# osso.net
KiCad netlist of a schematic drawn in EAGLE
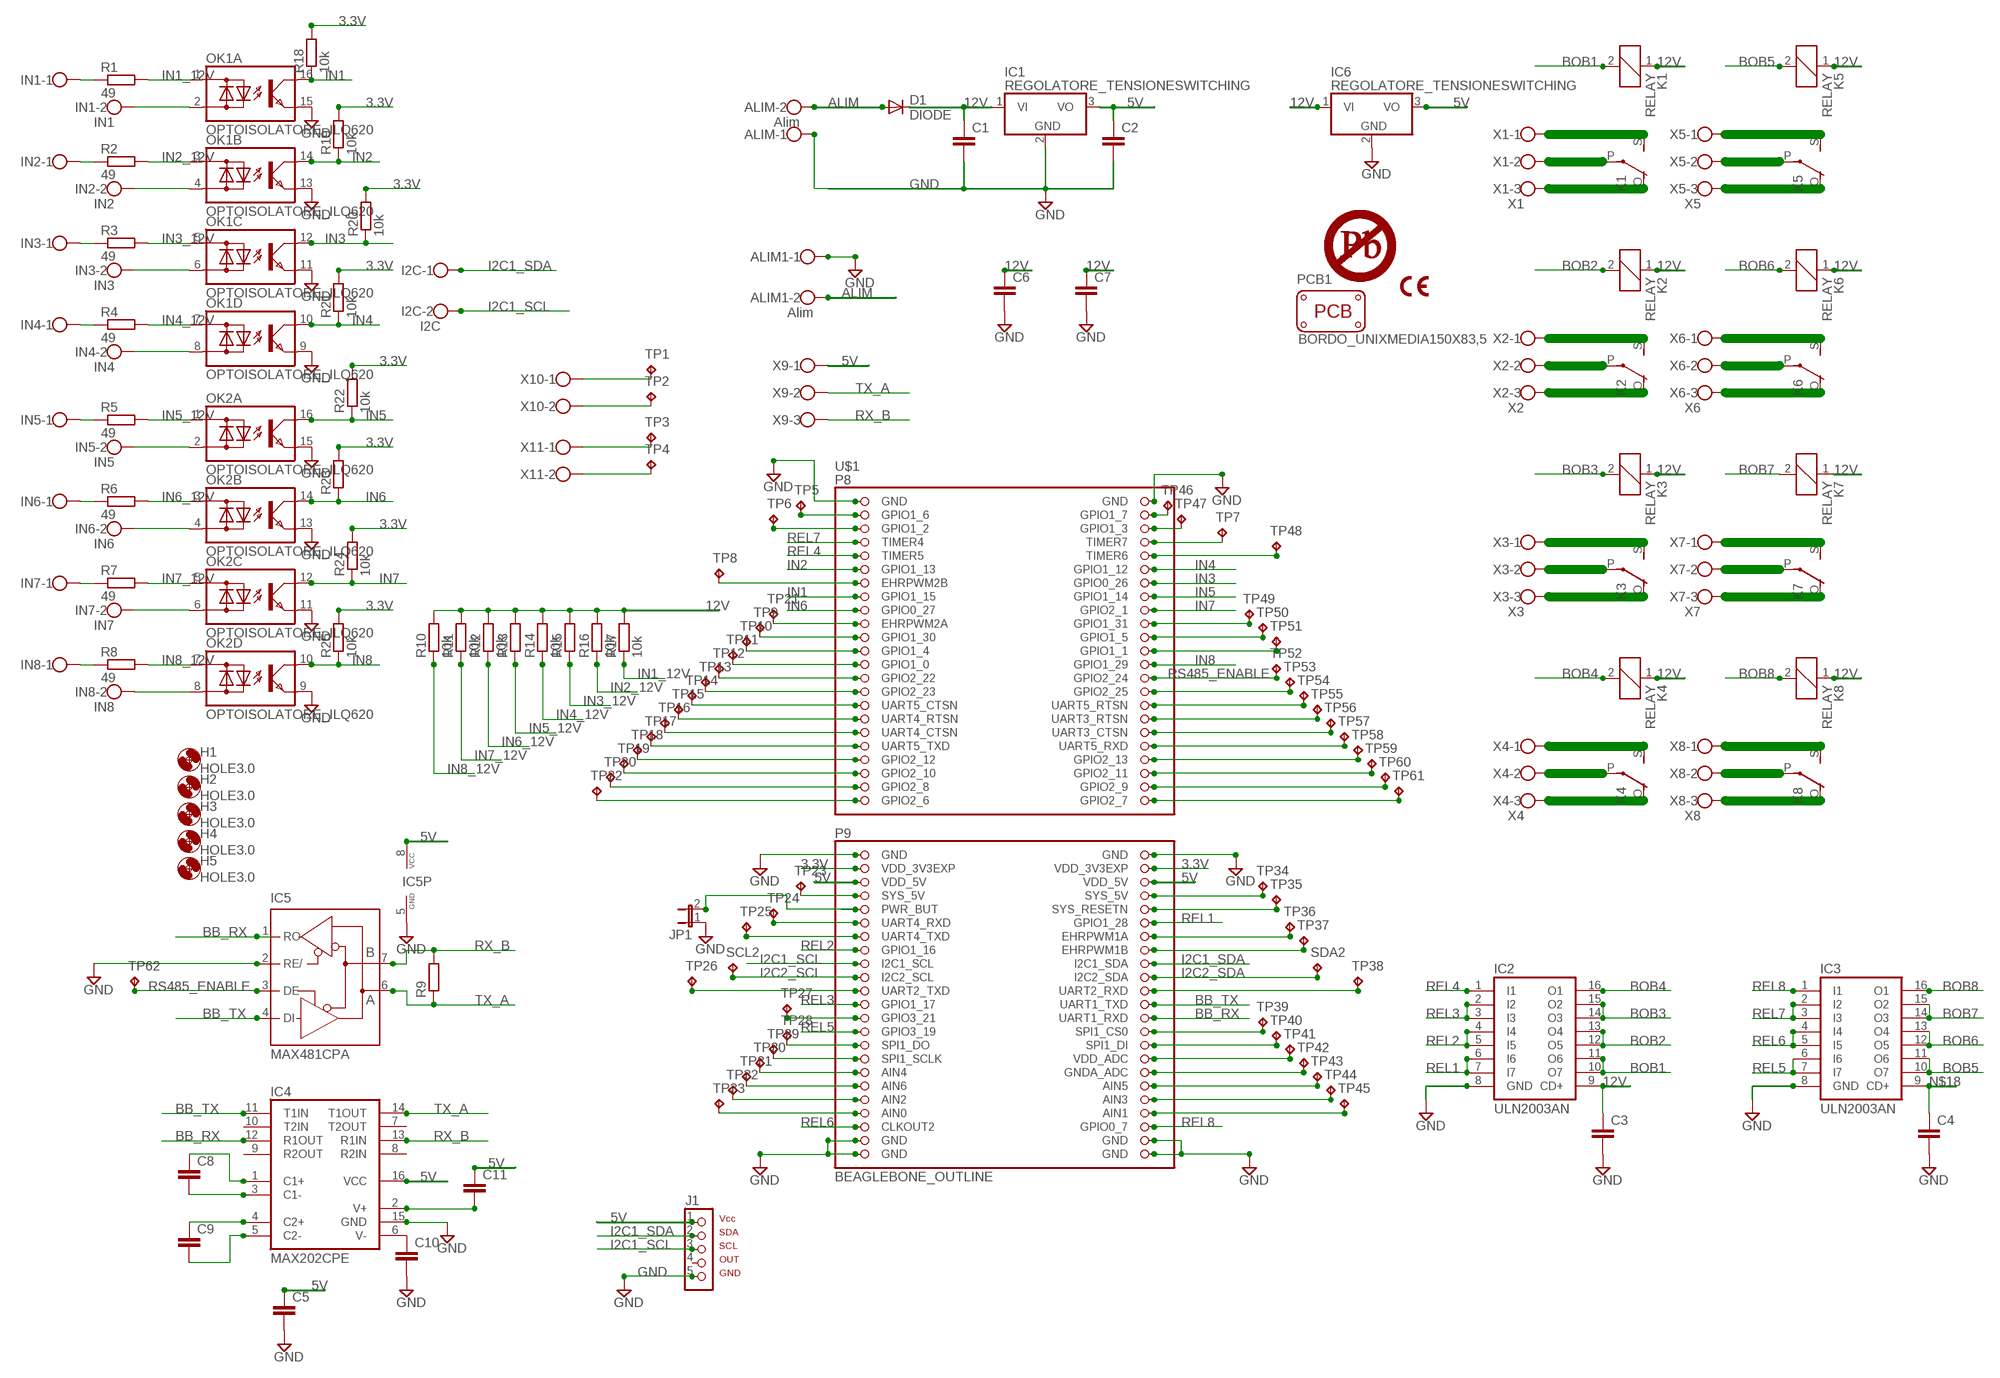
[diagram p0: schematic, sheet 1]

(export (version "E")
  (design (tool "Eeschema 10.0.6"))
  (components
    (comp (ref "ALIM")
      (value "Alim")
      (footprint "eagle-import:W237-102")
      (fields (field (name "MPN") "237-102"))
      (libsource (lib "eagle-import") (part "MORSETTO_2"))
    )
    (comp (ref "ALIM1")
      (value "Alim")
      (footprint "eagle-import:W237-102")
      (fields
        (field (name "MPN") "237-102")
        (field (name "MPN_1") "237-102")
        (field (name "OC_FARNELL") "unknown")
        (field (name "OC_NEWARK") "70K9898")
      )
      (libsource (lib "eagle-import") (part "MORSETTO_2"))
    )
    (comp (ref "C1")
      (value "C5/2.5")
      (footprint "eagle-import:C5B2.5")
      (libsource (lib "eagle-import") (part "C5/2.5"))
    )
    (comp (ref "C2")
      (value "C5/2.5")
      (footprint "eagle-import:C5B2.5")
      (libsource (lib "eagle-import") (part "C5/2.5"))
    )
    (comp (ref "C3")
      (value "C5/2.5")
      (footprint "eagle-import:C5B2.5")
      (libsource (lib "eagle-import") (part "C5/2.5"))
    )
    (comp (ref "C4")
      (value "C5/2.5")
      (footprint "eagle-import:C5B2.5")
      (libsource (lib "eagle-import") (part "C5/2.5"))
    )
    (comp (ref "C5")
      (value "C5/2.5")
      (footprint "eagle-import:C5B2.5")
      (libsource (lib "eagle-import") (part "C5/2.5"))
    )
    (comp (ref "C6")
      (value "C5/2.5")
      (footprint "eagle-import:C5B2.5")
      (libsource (lib "eagle-import") (part "C5/2.5"))
    )
    (comp (ref "C7")
      (value "C5/2.5")
      (footprint "eagle-import:C5B2.5")
      (libsource (lib "eagle-import") (part "C5/2.5"))
    )
    (comp (ref "C8")
      (value "C5/2.5")
      (footprint "eagle-import:C5B2.5")
      (libsource (lib "eagle-import") (part "C5/2.5"))
    )
    (comp (ref "C9")
      (value "C5/2.5")
      (footprint "eagle-import:C5B2.5")
      (libsource (lib "eagle-import") (part "C5/2.5"))
    )
    (comp (ref "C10")
      (value "C5/2.5")
      (footprint "eagle-import:C5B2.5")
      (libsource (lib "eagle-import") (part "C5/2.5"))
    )
    (comp (ref "C11")
      (value "C5/2.5")
      (footprint "eagle-import:C5B2.5")
      (libsource (lib "eagle-import") (part "C5/2.5"))
    )
    (comp (ref "D1")
      (value "DIODE")
      (footprint "eagle-import:DO15-12")
      (libsource (lib "eagle-import") (part "DIODE"))
    )
    (comp (ref "H1")
      (value "HOLE3.0")
      (footprint "eagle-import:3,0")
      (libsource (lib "eagle-import") (part "HOLE3.0"))
    )
    (comp (ref "H2")
      (value "HOLE3.0")
      (footprint "eagle-import:3,0")
      (libsource (lib "eagle-import") (part "HOLE3.0"))
    )
    (comp (ref "H3")
      (value "HOLE3.0")
      (footprint "eagle-import:3,0")
      (libsource (lib "eagle-import") (part "HOLE3.0"))
    )
    (comp (ref "H4")
      (value "HOLE3.0")
      (footprint "eagle-import:3,0")
      (libsource (lib "eagle-import") (part "HOLE3.0"))
    )
    (comp (ref "H5")
      (value "HOLE3.0")
      (footprint "eagle-import:3,0")
      (libsource (lib "eagle-import") (part "HOLE3.0"))
    )
    (comp (ref "I2C")
      (value "I2C")
      (footprint "eagle-import:W237-102")
      (fields
        (field (name "MPN") "237-102")
        (field (name "MPN_1") "237-102")
        (field (name "OC_FARNELL") "unknown")
        (field (name "OC_NEWARK") "70K9898")
      )
      (libsource (lib "eagle-import") (part "MORSETTO_2"))
    )
    (comp (ref "IC1")
      (value "REGOLATORE_TENSIONESWITCHING")
      (footprint "eagle-import:MT6-3")
      (libsource (lib "eagle-import") (part "REGOLATORE_TENSIONESWITCHING"))
    )
    (comp (ref "IC2")
      (value "ULN2003AN")
      (footprint "eagle-import:DIL16")
      (libsource (lib "eagle-import") (part "ULN2003AN"))
    )
    (comp (ref "IC3")
      (value "ULN2003AN")
      (footprint "eagle-import:DIL16")
      (libsource (lib "eagle-import") (part "ULN2003AN"))
    )
    (comp (ref "IC4")
      (value "MAX202CPE")
      (footprint "eagle-import:DIL16")
      (fields (field (name "MF") "MAXIM") (field (name "MPN") "MAX202CPE+"))
      (libsource (lib "eagle-import") (part "MAX202CPE"))
    )
    (comp (ref "IC5")
      (value "MAX481CPA")
      (footprint "eagle-import:DIL08")
      (fields (field (name "MPN") "MAX481CPA+"))
      (libsource (lib "eagle-import") (part "MAX481CPA"))
    )
    (comp (ref "IC6")
      (value "REGOLATORE_TENSIONESWITCHING")
      (footprint "eagle-import:MT6-3")
      (libsource (lib "eagle-import") (part "REGOLATORE_TENSIONESWITCHING"))
    )
    (comp (ref "IN1")
      (value "IN1")
      (footprint "eagle-import:W237-102")
      (fields (field (name "MPN") "237-102"))
      (libsource (lib "eagle-import") (part "MORSETTO_2"))
    )
    (comp (ref "IN2")
      (value "IN2")
      (footprint "eagle-import:W237-102")
      (fields (field (name "MPN") "237-102"))
      (libsource (lib "eagle-import") (part "MORSETTO_2"))
    )
    (comp (ref "IN3")
      (value "IN3")
      (footprint "eagle-import:W237-102")
      (fields (field (name "MPN") "237-102"))
      (libsource (lib "eagle-import") (part "MORSETTO_2"))
    )
    (comp (ref "IN4")
      (value "IN4")
      (footprint "eagle-import:W237-102")
      (fields (field (name "MPN") "237-102"))
      (libsource (lib "eagle-import") (part "MORSETTO_2"))
    )
    (comp (ref "IN5")
      (value "IN5")
      (footprint "eagle-import:W237-102")
      (fields (field (name "MPN") "237-102"))
      (libsource (lib "eagle-import") (part "MORSETTO_2"))
    )
    (comp (ref "IN6")
      (value "IN6")
      (footprint "eagle-import:W237-102")
      (fields (field (name "MPN") "237-102"))
      (libsource (lib "eagle-import") (part "MORSETTO_2"))
    )
    (comp (ref "IN7")
      (value "IN7")
      (footprint "eagle-import:W237-102")
      (fields (field (name "MPN") "237-102"))
      (libsource (lib "eagle-import") (part "MORSETTO_2"))
    )
    (comp (ref "IN8")
      (value "IN8")
      (footprint "eagle-import:W237-102")
      (fields (field (name "MPN") "237-102"))
      (libsource (lib "eagle-import") (part "MORSETTO_2"))
    )
    (comp (ref "J1")
      (value "RTC_MICROROBOT_ALGOZINO-PTH")
      (footprint "eagle-import:RTC_MICROBOT_ALGOZINO")
      (libsource (lib "eagle-import") (part "RTC_MICROROBOT_ALGOZINO-PTH"))
    )
    (comp (ref "JP1")
      (value "JUMPER_2")
      (footprint "eagle-import:JP1")
      (libsource (lib "eagle-import") (part "JUMPER_2"))
    )
    (comp (ref "K1")
      (value "RELAY")
      (footprint "eagle-import:G5LE")
      (libsource (lib "eagle-import") (part "My_Library_RELAY"))
    )
    (comp (ref "K2")
      (value "RELAY")
      (footprint "eagle-import:G5LE")
      (libsource (lib "eagle-import") (part "My_Library_RELAY"))
    )
    (comp (ref "K3")
      (value "RELAY")
      (footprint "eagle-import:G5LE")
      (libsource (lib "eagle-import") (part "My_Library_RELAY"))
    )
    (comp (ref "K4")
      (value "RELAY")
      (footprint "eagle-import:G5LE")
      (libsource (lib "eagle-import") (part "My_Library_RELAY"))
    )
    (comp (ref "K5")
      (value "RELAY")
      (footprint "eagle-import:G5LE")
      (libsource (lib "eagle-import") (part "My_Library_RELAY"))
    )
    (comp (ref "K6")
      (value "RELAY")
      (footprint "eagle-import:G5LE")
      (libsource (lib "eagle-import") (part "My_Library_RELAY"))
    )
    (comp (ref "K7")
      (value "RELAY")
      (footprint "eagle-import:G5LE")
      (libsource (lib "eagle-import") (part "RELAY"))
    )
    (comp (ref "K8")
      (value "RELAY")
      (footprint "eagle-import:G5LE")
      (libsource (lib "eagle-import") (part "My_Library_RELAY"))
    )
    (comp (ref "OK1")
      (value "OPTOISOLATORE_ILQ620")
      (footprint "eagle-import:DIL16")
      (fields (field (name "MF") "VISHAY/TELEFUNKEN") (field (name "MPN") "ILQ620"))
      (libsource (lib "eagle-import") (part "OPTOISOLATORE_ILQ620"))
    )
    (comp (ref "OK2")
      (value "OPTOISOLATORE_ILQ620")
      (footprint "eagle-import:DIL16")
      (fields (field (name "MF") "VISHAY/TELEFUNKEN") (field (name "MPN") "ILQ620"))
      (libsource (lib "eagle-import") (part "OPTOISOLATORE_ILQ620"))
    )
    (comp (ref "PCB1")
      (value "BORDO_UNIXMEDIA150X83,5")
      (footprint "eagle-import:BORD_UNIXMEDIA")
      (libsource (lib "eagle-import") (part "BORDO_UNIXMEDIA150X83,5"))
    )
    (comp (ref "R1")
      (value "49")
      (footprint "eagle-import:0204_7")
      (libsource (lib "eagle-import") (part "RESISTOR0204/7"))
    )
    (comp (ref "R2")
      (value "49")
      (footprint "eagle-import:0204_7")
      (libsource (lib "eagle-import") (part "RESISTOR0204/7"))
    )
    (comp (ref "R3")
      (value "49")
      (footprint "eagle-import:0204_7")
      (libsource (lib "eagle-import") (part "RESISTOR0204/7"))
    )
    (comp (ref "R4")
      (value "49")
      (footprint "eagle-import:0204_7")
      (libsource (lib "eagle-import") (part "RESISTOR0204/7"))
    )
    (comp (ref "R5")
      (value "49")
      (footprint "eagle-import:0204_7")
      (libsource (lib "eagle-import") (part "RESISTOR0204/7"))
    )
    (comp (ref "R6")
      (value "49")
      (footprint "eagle-import:0204_7")
      (libsource (lib "eagle-import") (part "RESISTOR0204/7"))
    )
    (comp (ref "R7")
      (value "49")
      (footprint "eagle-import:0204_7")
      (libsource (lib "eagle-import") (part "RESISTOR0204/7"))
    )
    (comp (ref "R8")
      (value "49")
      (footprint "eagle-import:0204_7")
      (libsource (lib "eagle-import") (part "RESISTOR0204/7"))
    )
    (comp (ref "R9")
      (value "RESISTOR0204/7")
      (footprint "eagle-import:0204_7")
      (libsource (lib "eagle-import") (part "RESISTOR0204/7"))
    )
    (comp (ref "R10")
      (value "10k")
      (footprint "eagle-import:0204_7")
      (libsource (lib "eagle-import") (part "RESISTOR0204/7"))
    )
    (comp (ref "R11")
      (value "10k")
      (footprint "eagle-import:0204_7")
      (libsource (lib "eagle-import") (part "RESISTOR0204/7"))
    )
    (comp (ref "R12")
      (value "10k")
      (footprint "eagle-import:0204_7")
      (libsource (lib "eagle-import") (part "RESISTOR0204/7"))
    )
    (comp (ref "R13")
      (value "RESISTOR0204/7")
      (footprint "eagle-import:0204_7")
      (libsource (lib "eagle-import") (part "RESISTOR0204/7"))
    )
    (comp (ref "R14")
      (value "10k")
      (footprint "eagle-import:0204_7")
      (libsource (lib "eagle-import") (part "RESISTOR0204/7"))
    )
    (comp (ref "R15")
      (value "RESISTOR0204/7")
      (footprint "eagle-import:0204_7")
      (libsource (lib "eagle-import") (part "RESISTOR0204/7"))
    )
    (comp (ref "R16")
      (value "10k")
      (footprint "eagle-import:0204_7")
      (libsource (lib "eagle-import") (part "RESISTOR0204/7"))
    )
    (comp (ref "R17")
      (value "10k")
      (footprint "eagle-import:0204_7")
      (libsource (lib "eagle-import") (part "RESISTOR0204/7"))
    )
    (comp (ref "R18")
      (value "10k")
      (footprint "eagle-import:0204_7")
      (libsource (lib "eagle-import") (part "RESISTOR0204/7"))
    )
    (comp (ref "R19")
      (value "10k")
      (footprint "eagle-import:0204_7")
      (libsource (lib "eagle-import") (part "RESISTOR0204/7"))
    )
    (comp (ref "R20")
      (value "10k")
      (footprint "eagle-import:0204_7")
      (libsource (lib "eagle-import") (part "RESISTOR0204/7"))
    )
    (comp (ref "R21")
      (value "10k")
      (footprint "eagle-import:0204_7")
      (libsource (lib "eagle-import") (part "RESISTOR0204/7"))
    )
    (comp (ref "R22")
      (value "10k")
      (footprint "eagle-import:0204_7")
      (libsource (lib "eagle-import") (part "RESISTOR0204/7"))
    )
    (comp (ref "R23")
      (value "RESISTOR0204/7")
      (footprint "eagle-import:0204_7")
      (libsource (lib "eagle-import") (part "RESISTOR0204/7"))
    )
    (comp (ref "R24")
      (value "10k")
      (footprint "eagle-import:0204_7")
      (libsource (lib "eagle-import") (part "RESISTOR0204/7"))
    )
    (comp (ref "R25")
      (value "10k")
      (footprint "eagle-import:0204_7")
      (libsource (lib "eagle-import") (part "RESISTOR0204/7"))
    )
    (comp (ref "SCL2")
      (value "TPPAD1-13")
      (footprint "eagle-import:TEST_POINT")
      (libsource (lib "eagle-import") (part "TPPAD1-13"))
    )
    (comp (ref "SDA2")
      (value "TP1")
      (footprint "eagle-import:TEST_POINT")
      (libsource (lib "eagle-import") (part "TPPAD1-13"))
    )
    (comp (ref "SS1")
      (value "CE-MARK")
      (footprint "eagle-import:CE-MARK-0.2")
      (libsource (lib "eagle-import") (part "CE-MARK"))
    )
    (comp (ref "SS2")
      (value "PB-MARK")
      (footprint "eagle-import:PB-MARK-0.2")
      (libsource (lib "eagle-import") (part "PB-MARK"))
    )
    (comp (ref "TP1")
      (value "TPPAD1-13")
      (footprint "eagle-import:TEST_POINT")
      (libsource (lib "eagle-import") (part "TPPAD1-13"))
    )
    (comp (ref "TP2")
      (value "TPPAD1-13")
      (footprint "eagle-import:TEST_POINT")
      (libsource (lib "eagle-import") (part "TPPAD1-13"))
    )
    (comp (ref "TP3")
      (value "TPPAD1-13")
      (footprint "eagle-import:TEST_POINT")
      (libsource (lib "eagle-import") (part "TPPAD1-13"))
    )
    (comp (ref "TP4")
      (value "TPPAD1-13")
      (footprint "eagle-import:TEST_POINT")
      (libsource (lib "eagle-import") (part "TPPAD1-13"))
    )
    (comp (ref "TP5")
      (value "TPPAD1-13")
      (footprint "eagle-import:TEST_POINT")
      (libsource (lib "eagle-import") (part "TPPAD1-13"))
    )
    (comp (ref "TP6")
      (value "TPPAD1-13")
      (footprint "eagle-import:TEST_POINT")
      (libsource (lib "eagle-import") (part "TPPAD1-13"))
    )
    (comp (ref "TP7")
      (value "TPPAD1-13")
      (footprint "eagle-import:TEST_POINT")
      (libsource (lib "eagle-import") (part "TPPAD1-13"))
    )
    (comp (ref "TP8")
      (value "TPPAD1-13")
      (footprint "eagle-import:TEST_POINT")
      (libsource (lib "eagle-import") (part "TPPAD1-13"))
    )
    (comp (ref "TP9")
      (value "TPPAD1-13")
      (footprint "eagle-import:TEST_POINT")
      (libsource (lib "eagle-import") (part "TPPAD1-13"))
    )
    (comp (ref "TP10")
      (value "TPPAD1-13")
      (footprint "eagle-import:TEST_POINT")
      (libsource (lib "eagle-import") (part "TPPAD1-13"))
    )
    (comp (ref "TP11")
      (value "TPPAD1-13")
      (footprint "eagle-import:TEST_POINT")
      (libsource (lib "eagle-import") (part "TPPAD1-13"))
    )
    (comp (ref "TP12")
      (value "TPPAD1-13")
      (footprint "eagle-import:TEST_POINT")
      (libsource (lib "eagle-import") (part "TPPAD1-13"))
    )
    (comp (ref "TP13")
      (value "TPPAD1-13")
      (footprint "eagle-import:TEST_POINT")
      (libsource (lib "eagle-import") (part "TPPAD1-13"))
    )
    (comp (ref "TP14")
      (value "TPPAD1-13")
      (footprint "eagle-import:TEST_POINT")
      (libsource (lib "eagle-import") (part "TPPAD1-13"))
    )
    (comp (ref "TP15")
      (value "TPPAD1-13")
      (footprint "eagle-import:TEST_POINT")
      (libsource (lib "eagle-import") (part "TPPAD1-13"))
    )
    (comp (ref "TP16")
      (value "TPPAD1-13")
      (footprint "eagle-import:TEST_POINT")
      (libsource (lib "eagle-import") (part "TPPAD1-13"))
    )
    (comp (ref "TP17")
      (value "TPPAD1-13")
      (footprint "eagle-import:TEST_POINT")
      (libsource (lib "eagle-import") (part "TPPAD1-13"))
    )
    (comp (ref "TP18")
      (value "TPPAD1-13")
      (footprint "eagle-import:TEST_POINT")
      (libsource (lib "eagle-import") (part "TPPAD1-13"))
    )
    (comp (ref "TP19")
      (value "TPPAD1-13")
      (footprint "eagle-import:TEST_POINT")
      (libsource (lib "eagle-import") (part "TPPAD1-13"))
    )
    (comp (ref "TP20")
      (value "TPPAD1-13")
      (footprint "eagle-import:TEST_POINT")
      (libsource (lib "eagle-import") (part "TPPAD1-13"))
    )
    (comp (ref "TP21")
      (value "TPPAD1-13")
      (footprint "eagle-import:TEST_POINT")
      (libsource (lib "eagle-import") (part "TPPAD1-13"))
    )
    (comp (ref "TP22")
      (value "TPPAD1-13")
      (footprint "eagle-import:TEST_POINT")
      (libsource (lib "eagle-import") (part "TPPAD1-13"))
    )
    (comp (ref "TP23")
      (value "TPPAD1-13")
      (footprint "eagle-import:TEST_POINT")
      (libsource (lib "eagle-import") (part "TPPAD1-13"))
    )
    (comp (ref "TP24")
      (value "TPPAD1-13")
      (footprint "eagle-import:TEST_POINT")
      (libsource (lib "eagle-import") (part "TPPAD1-13"))
    )
    (comp (ref "TP25")
      (value "TPPAD1-13")
      (footprint "eagle-import:TEST_POINT")
      (libsource (lib "eagle-import") (part "TPPAD1-13"))
    )
    (comp (ref "TP26")
      (value "TPPAD1-13")
      (footprint "eagle-import:TEST_POINT")
      (libsource (lib "eagle-import") (part "TPPAD1-13"))
    )
    (comp (ref "TP27")
      (value "TPPAD1-13")
      (footprint "eagle-import:TEST_POINT")
      (libsource (lib "eagle-import") (part "TPPAD1-13"))
    )
    (comp (ref "TP28")
      (value "TPPAD1-13")
      (footprint "eagle-import:TEST_POINT")
      (libsource (lib "eagle-import") (part "TPPAD1-13"))
    )
    (comp (ref "TP29")
      (value "TPPAD1-13")
      (footprint "eagle-import:TEST_POINT")
      (libsource (lib "eagle-import") (part "TPPAD1-13"))
    )
    (comp (ref "TP30")
      (value "TPPAD1-13")
      (footprint "eagle-import:TEST_POINT")
      (libsource (lib "eagle-import") (part "TPPAD1-13"))
    )
    (comp (ref "TP31")
      (value "TPPAD1-13")
      (footprint "eagle-import:TEST_POINT")
      (libsource (lib "eagle-import") (part "TPPAD1-13"))
    )
    (comp (ref "TP32")
      (value "TPPAD1-13")
      (footprint "eagle-import:TEST_POINT")
      (libsource (lib "eagle-import") (part "TPPAD1-13"))
    )
    (comp (ref "TP33")
      (value "TPPAD1-13")
      (footprint "eagle-import:TEST_POINT")
      (libsource (lib "eagle-import") (part "TPPAD1-13"))
    )
    (comp (ref "TP34")
      (value "TPPAD1-13")
      (footprint "eagle-import:TEST_POINT")
      (libsource (lib "eagle-import") (part "TPPAD1-13"))
    )
    (comp (ref "TP35")
      (value "TPPAD1-13")
      (footprint "eagle-import:TEST_POINT")
      (libsource (lib "eagle-import") (part "TPPAD1-13"))
    )
    (comp (ref "TP36")
      (value "TPPAD1-13")
      (footprint "eagle-import:TEST_POINT")
      (libsource (lib "eagle-import") (part "TPPAD1-13"))
    )
    (comp (ref "TP37")
      (value "TPPAD1-13")
      (footprint "eagle-import:TEST_POINT")
      (libsource (lib "eagle-import") (part "TPPAD1-13"))
    )
    (comp (ref "TP38")
      (value "TPPAD1-13")
      (footprint "eagle-import:TEST_POINT")
      (libsource (lib "eagle-import") (part "TPPAD1-13"))
    )
    (comp (ref "TP39")
      (value "TPPAD1-13")
      (footprint "eagle-import:TEST_POINT")
      (libsource (lib "eagle-import") (part "TPPAD1-13"))
    )
    (comp (ref "TP40")
      (value "TPPAD1-13")
      (footprint "eagle-import:TEST_POINT")
      (libsource (lib "eagle-import") (part "TPPAD1-13"))
    )
    (comp (ref "TP41")
      (value "TPPAD1-13")
      (footprint "eagle-import:TEST_POINT")
      (libsource (lib "eagle-import") (part "TPPAD1-13"))
    )
    (comp (ref "TP42")
      (value "TPPAD1-13")
      (footprint "eagle-import:TEST_POINT")
      (libsource (lib "eagle-import") (part "TPPAD1-13"))
    )
    (comp (ref "TP43")
      (value "TPPAD1-13")
      (footprint "eagle-import:TEST_POINT")
      (libsource (lib "eagle-import") (part "TPPAD1-13"))
    )
    (comp (ref "TP44")
      (value "TPPAD1-13")
      (footprint "eagle-import:TEST_POINT")
      (libsource (lib "eagle-import") (part "TPPAD1-13"))
    )
    (comp (ref "TP45")
      (value "TPPAD1-13")
      (footprint "eagle-import:TEST_POINT")
      (libsource (lib "eagle-import") (part "TPPAD1-13"))
    )
    (comp (ref "TP46")
      (value "TPPAD1-13")
      (footprint "eagle-import:TEST_POINT")
      (libsource (lib "eagle-import") (part "TPPAD1-13"))
    )
    (comp (ref "TP47")
      (value "TPPAD1-13")
      (footprint "eagle-import:TEST_POINT")
      (libsource (lib "eagle-import") (part "TPPAD1-13"))
    )
    (comp (ref "TP48")
      (value "TPPAD1-13")
      (footprint "eagle-import:TEST_POINT")
      (libsource (lib "eagle-import") (part "TPPAD1-13"))
    )
    (comp (ref "TP49")
      (value "TPPAD1-13")
      (footprint "eagle-import:TEST_POINT")
      (libsource (lib "eagle-import") (part "TPPAD1-13"))
    )
    (comp (ref "TP50")
      (value "TPPAD1-13")
      (footprint "eagle-import:TEST_POINT")
      (libsource (lib "eagle-import") (part "TPPAD1-13"))
    )
    (comp (ref "TP51")
      (value "TPPAD1-13")
      (footprint "eagle-import:TEST_POINT")
      (libsource (lib "eagle-import") (part "TPPAD1-13"))
    )
    (comp (ref "TP52")
      (value "TPPAD1-13")
      (footprint "eagle-import:TEST_POINT")
      (libsource (lib "eagle-import") (part "TPPAD1-13"))
    )
    (comp (ref "TP53")
      (value "TPPAD1-13")
      (footprint "eagle-import:TEST_POINT")
      (libsource (lib "eagle-import") (part "TPPAD1-13"))
    )
    (comp (ref "TP54")
      (value "TPPAD1-13")
      (footprint "eagle-import:TEST_POINT")
      (libsource (lib "eagle-import") (part "TPPAD1-13"))
    )
    (comp (ref "TP55")
      (value "TPPAD1-13")
      (footprint "eagle-import:TEST_POINT")
      (libsource (lib "eagle-import") (part "TPPAD1-13"))
    )
    (comp (ref "TP56")
      (value "TPPAD1-13")
      (footprint "eagle-import:TEST_POINT")
      (libsource (lib "eagle-import") (part "TPPAD1-13"))
    )
    (comp (ref "TP57")
      (value "TPPAD1-13")
      (footprint "eagle-import:TEST_POINT")
      (libsource (lib "eagle-import") (part "TPPAD1-13"))
    )
    (comp (ref "TP58")
      (value "TPPAD1-13")
      (footprint "eagle-import:TEST_POINT")
      (libsource (lib "eagle-import") (part "TPPAD1-13"))
    )
    (comp (ref "TP59")
      (value "TPPAD1-13")
      (footprint "eagle-import:TEST_POINT")
      (libsource (lib "eagle-import") (part "TPPAD1-13"))
    )
    (comp (ref "TP60")
      (value "TPPAD1-13")
      (footprint "eagle-import:TEST_POINT")
      (libsource (lib "eagle-import") (part "TPPAD1-13"))
    )
    (comp (ref "TP61")
      (value "TPPAD1-13")
      (footprint "eagle-import:TEST_POINT")
      (libsource (lib "eagle-import") (part "TPPAD1-13"))
    )
    (comp (ref "TP62")
      (value "TPPAD1-13")
      (footprint "eagle-import:TEST_POINT")
      (libsource (lib "eagle-import") (part "TPPAD1-13"))
    )
    (comp (ref "U$1")
      (value "BEAGLEBONE_OUTLINE")
      (footprint "eagle-import:BEAGLEBONE_SHIELD")
      (libsource (lib "eagle-import") (part "BEAGLEBONE_OUTLINE"))
    )
    (comp (ref "X1")
      (value "X1")
      (footprint "eagle-import:W237-103")
      (fields (field (name "MPN") "237-103"))
      (libsource (lib "eagle-import") (part "MORSETTO_3"))
    )
    (comp (ref "X2")
      (value "X2")
      (footprint "eagle-import:W237-103")
      (fields (field (name "MPN") "237-103"))
      (libsource (lib "eagle-import") (part "MORSETTO_3"))
    )
    (comp (ref "X3")
      (value "X3")
      (footprint "eagle-import:W237-103")
      (fields (field (name "MPN") "237-103"))
      (libsource (lib "eagle-import") (part "MORSETTO_3"))
    )
    (comp (ref "X4")
      (value "X4")
      (footprint "eagle-import:W237-103")
      (fields (field (name "MPN") "237-103"))
      (libsource (lib "eagle-import") (part "MORSETTO_3"))
    )
    (comp (ref "X5")
      (value "X5")
      (footprint "eagle-import:W237-103")
      (fields (field (name "MPN") "237-103"))
      (libsource (lib "eagle-import") (part "MORSETTO_3"))
    )
    (comp (ref "X6")
      (value "X6")
      (footprint "eagle-import:W237-103")
      (fields (field (name "MPN") "237-103"))
      (libsource (lib "eagle-import") (part "MORSETTO_3"))
    )
    (comp (ref "X7")
      (value "X7")
      (footprint "eagle-import:W237-103")
      (fields (field (name "MPN") "237-103"))
      (libsource (lib "eagle-import") (part "MORSETTO_3"))
    )
    (comp (ref "X8")
      (value "X8")
      (footprint "eagle-import:W237-103")
      (fields (field (name "MPN") "237-103"))
      (libsource (lib "eagle-import") (part "MORSETTO_3"))
    )
    (comp (ref "X9")
      (value "MORSETTO_3")
      (footprint "eagle-import:W237-103")
      (fields (field (name "MPN") "237-103"))
      (libsource (lib "eagle-import") (part "MORSETTO_3"))
    )
    (comp (ref "X10")
      (value "MORSETTO_2")
      (footprint "eagle-import:W237-102")
      (fields (field (name "MPN") "237-102"))
      (libsource (lib "eagle-import") (part "MORSETTO_2"))
    )
    (comp (ref "X11")
      (value "MORSETTO_2")
      (footprint "eagle-import:W237-102")
      (fields (field (name "MPN") "237-102"))
      (libsource (lib "eagle-import") (part "MORSETTO_2"))
    )
  )
  (nets
    (net (code "1") (name "/3.3V") (class "Default")
      (node (ref "R18") (pin "2") (pinfunction "2_2") (pintype "passive"))
      (node (ref "R19") (pin "2") (pinfunction "2_2") (pintype "passive"))
      (node (ref "R20") (pin "2") (pinfunction "2_2") (pintype "passive"))
      (node (ref "R21") (pin "2") (pinfunction "2_2") (pintype "passive"))
      (node (ref "R22") (pin "2") (pinfunction "2_2") (pintype "passive"))
      (node (ref "R23") (pin "2") (pinfunction "2_2") (pintype "passive"))
      (node (ref "R24") (pin "2") (pinfunction "2_2") (pintype "passive"))
      (node (ref "R25") (pin "2") (pinfunction "2_2") (pintype "passive"))
      (node (ref "U$1") (pin "49") (pinfunction "VDD_3V3EXP_49") (pintype "power_in"))
      (node (ref "U$1") (pin "50") (pinfunction "VDD_3V3EXP_50") (pintype "power_in"))
    )
    (net (code "2") (name "/5V") (class "Default")
      (node (ref "C11") (pin "1") (pinfunction "1_1") (pintype "passive"))
      (node (ref "C2") (pin "1") (pinfunction "1_1") (pintype "passive"))
      (node (ref "C5") (pin "1") (pinfunction "1_1") (pintype "passive"))
      (node (ref "IC1") (pin "3") (pinfunction "VO_3") (pintype "passive"))
      (node (ref "IC4") (pin "16") (pinfunction "VCC_16") (pintype "power_in"))
      (node (ref "IC5") (pin "8") (pinfunction "VCC_8") (pintype "power_in"))
      (node (ref "IC6") (pin "3") (pinfunction "VO_3") (pintype "passive"))
      (node (ref "J1") (pin "1") (pinfunction "1_1") (pintype "bidirectional"))
      (node (ref "U$1") (pin "51") (pinfunction "VDD_5V_51") (pintype "power_in"))
      (node (ref "U$1") (pin "52") (pinfunction "VDD_5V_52") (pintype "power_in"))
      (node (ref "X9") (pin "1") (pinfunction "KL_1") (pintype "passive"))
    )
    (net (code "3") (name "/12V") (class "Default")
      (node (ref "C1") (pin "1") (pinfunction "1_1") (pintype "passive"))
      (node (ref "C3") (pin "1") (pinfunction "1_1") (pintype "passive"))
      (node (ref "C6") (pin "1") (pinfunction "1_1") (pintype "passive"))
      (node (ref "C7") (pin "1") (pinfunction "1_1") (pintype "passive"))
      (node (ref "D1") (pin "C") (pinfunction "C_C") (pintype "passive"))
      (node (ref "IC1") (pin "1") (pinfunction "VI_1") (pintype "input"))
      (node (ref "IC2") (pin "9") (pinfunction "CD+_9") (pintype "passive"))
      (node (ref "IC6") (pin "1") (pinfunction "VI_1") (pintype "input"))
      (node (ref "K1") (pin "1") (pinfunction "1_1") (pintype "passive"))
      (node (ref "K2") (pin "1") (pinfunction "1_1") (pintype "passive"))
      (node (ref "K3") (pin "1") (pinfunction "1_1") (pintype "passive"))
      (node (ref "K4") (pin "1") (pinfunction "1_1") (pintype "passive"))
      (node (ref "K5") (pin "1") (pinfunction "1_1") (pintype "passive"))
      (node (ref "K6") (pin "1") (pinfunction "1_1") (pintype "passive"))
      (node (ref "K7") (pin "1") (pinfunction "1_1") (pintype "passive"))
      (node (ref "K8") (pin "1") (pinfunction "1_1") (pintype "passive"))
      (node (ref "R10") (pin "2") (pinfunction "2_2") (pintype "passive"))
      (node (ref "R11") (pin "2") (pinfunction "2_2") (pintype "passive"))
      (node (ref "R12") (pin "2") (pinfunction "2_2") (pintype "passive"))
      (node (ref "R13") (pin "2") (pinfunction "2_2") (pintype "passive"))
      (node (ref "R14") (pin "2") (pinfunction "2_2") (pintype "passive"))
      (node (ref "R15") (pin "2") (pinfunction "2_2") (pintype "passive"))
      (node (ref "R16") (pin "2") (pinfunction "2_2") (pintype "passive"))
      (node (ref "R17") (pin "2") (pinfunction "2_2") (pintype "passive"))
    )
    (net (code "4") (name "/ALIM") (class "Default")
      (node (ref "ALIM") (pin "2") (pinfunction "KL_2") (pintype "passive"))
      (node (ref "ALIM1") (pin "2") (pinfunction "KL_2") (pintype "passive"))
      (node (ref "D1") (pin "A") (pinfunction "A_A") (pintype "passive"))
    )
    (net (code "5") (name "/BB_RX") (class "Default")
      (node (ref "IC4") (pin "12") (pinfunction "R1OUT_12") (pintype "output"))
      (node (ref "IC5") (pin "1") (pinfunction "RO_1") (pintype "output"))
      (node (ref "U$1") (pin "72") (pinfunction "UART1_RXD_72") (pintype "passive"))
    )
    (net (code "6") (name "/BB_TX") (class "Default")
      (node (ref "IC4") (pin "11") (pinfunction "T1IN_11") (pintype "input"))
      (node (ref "IC5") (pin "4") (pinfunction "DI_4") (pintype "input"))
      (node (ref "U$1") (pin "70") (pinfunction "UART1_TXD_70") (pintype "passive"))
    )
    (net (code "7") (name "/BOB1") (class "Default")
      (node (ref "IC2") (pin "10") (pinfunction "O7_10") (pintype "open_collector"))
      (node (ref "IC2") (pin "11") (pinfunction "O6_11") (pintype "open_collector"))
      (node (ref "K1") (pin "2") (pinfunction "2_2") (pintype "passive"))
    )
    (net (code "8") (name "/BOB2") (class "Default")
      (node (ref "IC2") (pin "12") (pinfunction "O5_12") (pintype "open_collector"))
      (node (ref "IC2") (pin "13") (pinfunction "O4_13") (pintype "open_collector"))
      (node (ref "K2") (pin "2") (pinfunction "2_2") (pintype "passive"))
    )
    (net (code "9") (name "/BOB3") (class "Default")
      (node (ref "IC2") (pin "14") (pinfunction "O3_14") (pintype "open_collector"))
      (node (ref "IC2") (pin "15") (pinfunction "O2_15") (pintype "open_collector"))
      (node (ref "K3") (pin "2") (pinfunction "2_2") (pintype "passive"))
    )
    (net (code "10") (name "/BOB4") (class "Default")
      (node (ref "IC2") (pin "16") (pinfunction "O1_16") (pintype "open_collector"))
      (node (ref "K4") (pin "2") (pinfunction "2_2") (pintype "passive"))
    )
    (net (code "11") (name "/BOB5") (class "Default")
      (node (ref "IC3") (pin "10") (pinfunction "O7_10") (pintype "open_collector"))
      (node (ref "IC3") (pin "11") (pinfunction "O6_11") (pintype "open_collector"))
      (node (ref "K5") (pin "2") (pinfunction "2_2") (pintype "passive"))
    )
    (net (code "12") (name "/BOB6") (class "Default")
      (node (ref "IC3") (pin "12") (pinfunction "O5_12") (pintype "open_collector"))
      (node (ref "IC3") (pin "13") (pinfunction "O4_13") (pintype "open_collector"))
      (node (ref "K6") (pin "2") (pinfunction "2_2") (pintype "passive"))
    )
    (net (code "13") (name "/BOB7") (class "Default")
      (node (ref "IC3") (pin "14") (pinfunction "O3_14") (pintype "open_collector"))
      (node (ref "IC3") (pin "15") (pinfunction "O2_15") (pintype "open_collector"))
      (node (ref "K7") (pin "2") (pinfunction "2_2") (pintype "passive"))
    )
    (net (code "14") (name "/BOB8") (class "Default")
      (node (ref "IC3") (pin "16") (pinfunction "O1_16") (pintype "open_collector"))
      (node (ref "K8") (pin "2") (pinfunction "2_2") (pintype "passive"))
    )
    (net (code "15") (name "/I2C1_SCL") (class "Default")
      (node (ref "I2C") (pin "2") (pinfunction "KL_2") (pintype "passive"))
      (node (ref "J1") (pin "3") (pinfunction "3_3") (pintype "bidirectional"))
      (node (ref "U$1") (pin "63") (pinfunction "I2C1_SCL_63") (pintype "passive"))
    )
    (net (code "16") (name "/I2C1_SDA") (class "Default")
      (node (ref "I2C") (pin "1") (pinfunction "KL_1") (pintype "passive"))
      (node (ref "J1") (pin "2") (pinfunction "2_2") (pintype "bidirectional"))
      (node (ref "U$1") (pin "64") (pinfunction "I2C1_SDA_64") (pintype "passive"))
    )
    (net (code "17") (name "/I2C2_SCL") (class "Default")
      (node (ref "SCL2") (pin "TP") (pinfunction "TP_TP") (pintype "input"))
      (node (ref "U$1") (pin "65") (pinfunction "I2C2_SCL_65") (pintype "passive"))
    )
    (net (code "18") (name "/I2C2_SDA") (class "Default")
      (node (ref "SDA2") (pin "TP") (pinfunction "TP_TP") (pintype "input"))
      (node (ref "U$1") (pin "66") (pinfunction "I2C2_SDA_66") (pintype "passive"))
    )
    (net (code "19") (name "/IN1") (class "Default")
      (node (ref "OK1") (pin "16") (pinfunction "C_16") (pintype "passive"))
      (node (ref "R18") (pin "1") (pinfunction "1_1") (pintype "passive"))
      (node (ref "U$1") (pin "15") (pinfunction "GPIO1_15_15") (pintype "passive"))
    )
    (net (code "20") (name "/IN1_12V") (class "Default")
      (node (ref "OK1") (pin "1") (pinfunction "AC1_1") (pintype "passive"))
      (node (ref "R1") (pin "2") (pinfunction "2_2") (pintype "passive"))
      (node (ref "R17") (pin "1") (pinfunction "1_1") (pintype "passive"))
    )
    (net (code "21") (name "/IN2") (class "Default")
      (node (ref "OK1") (pin "14") (pinfunction "C_14") (pintype "passive"))
      (node (ref "R19") (pin "1") (pinfunction "1_1") (pintype "passive"))
      (node (ref "U$1") (pin "11") (pinfunction "GPIO1_13_11") (pintype "passive"))
    )
    (net (code "22") (name "/IN2_12V") (class "Default")
      (node (ref "OK1") (pin "3") (pinfunction "AC1_3") (pintype "passive"))
      (node (ref "R16") (pin "1") (pinfunction "1_1") (pintype "passive"))
      (node (ref "R2") (pin "2") (pinfunction "2_2") (pintype "passive"))
    )
    (net (code "23") (name "/IN3") (class "Default")
      (node (ref "OK1") (pin "12") (pinfunction "C_12") (pintype "passive"))
      (node (ref "R20") (pin "1") (pinfunction "1_1") (pintype "passive"))
      (node (ref "U$1") (pin "14") (pinfunction "GPIO0_26_14") (pintype "passive"))
    )
    (net (code "24") (name "/IN3_12V") (class "Default")
      (node (ref "OK1") (pin "5") (pinfunction "AC1_5") (pintype "passive"))
      (node (ref "R15") (pin "1") (pinfunction "1_1") (pintype "passive"))
      (node (ref "R3") (pin "2") (pinfunction "2_2") (pintype "passive"))
    )
    (net (code "25") (name "/IN4") (class "Default")
      (node (ref "OK1") (pin "10") (pinfunction "C_10") (pintype "passive"))
      (node (ref "R21") (pin "1") (pinfunction "1_1") (pintype "passive"))
      (node (ref "U$1") (pin "12") (pinfunction "GPIO1_12_12") (pintype "passive"))
    )
    (net (code "26") (name "/IN4_12V") (class "Default")
      (node (ref "OK1") (pin "7") (pinfunction "AC1_7") (pintype "passive"))
      (node (ref "R14") (pin "1") (pinfunction "1_1") (pintype "passive"))
      (node (ref "R4") (pin "2") (pinfunction "2_2") (pintype "passive"))
    )
    (net (code "27") (name "/IN5") (class "Default")
      (node (ref "OK2") (pin "16") (pinfunction "C_16") (pintype "passive"))
      (node (ref "R22") (pin "1") (pinfunction "1_1") (pintype "passive"))
      (node (ref "U$1") (pin "16") (pinfunction "GPIO1_14_16") (pintype "passive"))
    )
    (net (code "28") (name "/IN5_12V") (class "Default")
      (node (ref "OK2") (pin "1") (pinfunction "AC1_1") (pintype "passive"))
      (node (ref "R13") (pin "1") (pinfunction "1_1") (pintype "passive"))
      (node (ref "R5") (pin "2") (pinfunction "2_2") (pintype "passive"))
    )
    (net (code "29") (name "/IN6") (class "Default")
      (node (ref "OK2") (pin "14") (pinfunction "C_14") (pintype "passive"))
      (node (ref "R23") (pin "1") (pinfunction "1_1") (pintype "passive"))
      (node (ref "U$1") (pin "17") (pinfunction "GPIO0_27_17") (pintype "passive"))
    )
    (net (code "30") (name "/IN6_12V") (class "Default")
      (node (ref "OK2") (pin "3") (pinfunction "AC1_3") (pintype "passive"))
      (node (ref "R12") (pin "1") (pinfunction "1_1") (pintype "passive"))
      (node (ref "R6") (pin "2") (pinfunction "2_2") (pintype "passive"))
    )
    (net (code "31") (name "/IN7") (class "Default")
      (node (ref "OK2") (pin "12") (pinfunction "C_12") (pintype "passive"))
      (node (ref "R24") (pin "1") (pinfunction "1_1") (pintype "passive"))
      (node (ref "U$1") (pin "18") (pinfunction "GPIO2_1_18") (pintype "passive"))
    )
    (net (code "32") (name "/IN7_12V") (class "Default")
      (node (ref "OK2") (pin "5") (pinfunction "AC1_5") (pintype "passive"))
      (node (ref "R11") (pin "1") (pinfunction "1_1") (pintype "passive"))
      (node (ref "R7") (pin "2") (pinfunction "2_2") (pintype "passive"))
    )
    (net (code "33") (name "/IN8") (class "Default")
      (node (ref "OK2") (pin "10") (pinfunction "C_10") (pintype "passive"))
      (node (ref "R25") (pin "1") (pinfunction "1_1") (pintype "passive"))
      (node (ref "U$1") (pin "26") (pinfunction "GPIO1_29_26") (pintype "passive"))
    )
    (net (code "34") (name "/IN8_12V") (class "Default")
      (node (ref "OK2") (pin "7") (pinfunction "AC1_7") (pintype "passive"))
      (node (ref "R10") (pin "1") (pinfunction "1_1") (pintype "passive"))
      (node (ref "R8") (pin "2") (pinfunction "2_2") (pintype "passive"))
    )
    (net (code "35") (name "/N$18") (class "Default")
      (node (ref "C4") (pin "1") (pinfunction "1_1") (pintype "passive"))
      (node (ref "IC3") (pin "9") (pinfunction "CD+_9") (pintype "passive"))
    )
    (net (code "36") (name "/REL1") (class "Default")
      (node (ref "IC2") (pin "6") (pinfunction "I6_6") (pintype "input"))
      (node (ref "IC2") (pin "7") (pinfunction "I7_7") (pintype "input"))
      (node (ref "U$1") (pin "58") (pinfunction "GPIO1_28_58") (pintype "passive"))
    )
    (net (code "37") (name "/REL2") (class "Default")
      (node (ref "IC2") (pin "4") (pinfunction "I4_4") (pintype "input"))
      (node (ref "IC2") (pin "5") (pinfunction "I5_5") (pintype "input"))
      (node (ref "U$1") (pin "61") (pinfunction "GPIO1_16_61") (pintype "passive"))
    )
    (net (code "38") (name "/REL3") (class "Default")
      (node (ref "IC2") (pin "2") (pinfunction "I2_2") (pintype "input"))
      (node (ref "IC2") (pin "3") (pinfunction "I3_3") (pintype "input"))
      (node (ref "U$1") (pin "69") (pinfunction "GPIO1_17_69") (pintype "passive"))
    )
    (net (code "39") (name "/REL4") (class "Default")
      (node (ref "IC2") (pin "1") (pinfunction "I1_1") (pintype "input"))
      (node (ref "U$1") (pin "9") (pinfunction "TIMER5_9") (pintype "passive"))
    )
    (net (code "40") (name "/REL5") (class "Default")
      (node (ref "IC3") (pin "6") (pinfunction "I6_6") (pintype "input"))
      (node (ref "IC3") (pin "7") (pinfunction "I7_7") (pintype "input"))
      (node (ref "U$1") (pin "73") (pinfunction "GPIO3_19_73") (pintype "passive"))
    )
    (net (code "41") (name "/REL6") (class "Default")
      (node (ref "IC3") (pin "4") (pinfunction "I4_4") (pintype "input"))
      (node (ref "IC3") (pin "5") (pinfunction "I5_5") (pintype "input"))
      (node (ref "U$1") (pin "87") (pinfunction "CLKOUT2_87") (pintype "input"))
    )
    (net (code "42") (name "/REL7") (class "Default")
      (node (ref "IC3") (pin "2") (pinfunction "I2_2") (pintype "input"))
      (node (ref "IC3") (pin "3") (pinfunction "I3_3") (pintype "input"))
      (node (ref "U$1") (pin "7") (pinfunction "TIMER4_7") (pintype "passive"))
    )
    (net (code "43") (name "/REL8") (class "Default")
      (node (ref "IC3") (pin "1") (pinfunction "I1_1") (pintype "input"))
      (node (ref "U$1") (pin "88") (pinfunction "GPIO0_7_88") (pintype "passive"))
    )
    (net (code "44") (name "/RS485_ENABLE") (class "Default")
      (node (ref "IC5") (pin "3") (pinfunction "DE_3") (pintype "input"))
      (node (ref "TP52") (pin "TP") (pinfunction "TP_TP") (pintype "input"))
      (node (ref "TP62") (pin "TP") (pinfunction "TP_TP") (pintype "input"))
      (node (ref "U$1") (pin "28") (pinfunction "GPIO2_24_28") (pintype "passive"))
    )
    (net (code "45") (name "/RX_B") (class "Default")
      (node (ref "IC4") (pin "13") (pinfunction "R1IN_13") (pintype "input"))
      (node (ref "IC5") (pin "7") (pinfunction "B_7") (pintype "passive"))
      (node (ref "R9") (pin "2") (pinfunction "2_2") (pintype "passive"))
      (node (ref "X9") (pin "3") (pinfunction "KL_3") (pintype "passive"))
    )
    (net (code "46") (name "/TX_A") (class "Default")
      (node (ref "IC4") (pin "14") (pinfunction "T1OUT_14") (pintype "output"))
      (node (ref "IC5") (pin "6") (pinfunction "A_6") (pintype "passive"))
      (node (ref "R9") (pin "1") (pinfunction "1_1") (pintype "passive"))
      (node (ref "X9") (pin "2") (pinfunction "KL_2") (pintype "passive"))
    )
    (net (code "47") (name "GND") (class "Default")
      (node (ref "ALIM") (pin "1") (pinfunction "KL_1") (pintype "passive"))
      (node (ref "ALIM1") (pin "1") (pinfunction "KL_1") (pintype "passive"))
      (node (ref "C1") (pin "2") (pinfunction "2_2") (pintype "passive"))
      (node (ref "C10") (pin "2") (pinfunction "2_2") (pintype "passive"))
      (node (ref "C2") (pin "2") (pinfunction "2_2") (pintype "passive"))
      (node (ref "C3") (pin "2") (pinfunction "2_2") (pintype "passive"))
      (node (ref "C4") (pin "2") (pinfunction "2_2") (pintype "passive"))
      (node (ref "C5") (pin "2") (pinfunction "2_2") (pintype "passive"))
      (node (ref "C6") (pin "2") (pinfunction "2_2") (pintype "passive"))
      (node (ref "C7") (pin "2") (pinfunction "2_2") (pintype "passive"))
      (node (ref "IC1") (pin "2") (pinfunction "GND_2") (pintype "passive"))
      (node (ref "IC2") (pin "8") (pinfunction "GND_8") (pintype "power_in"))
      (node (ref "IC3") (pin "8") (pinfunction "GND_8") (pintype "power_in"))
      (node (ref "IC4") (pin "15") (pinfunction "GND_15") (pintype "power_in"))
      (node (ref "IC5") (pin "2") (pinfunction "RE/_2") (pintype "input"))
      (node (ref "IC5") (pin "5") (pinfunction "GND_5") (pintype "power_in"))
      (node (ref "IC6") (pin "2") (pinfunction "GND_2") (pintype "passive"))
      (node (ref "J1") (pin "5") (pinfunction "5_5") (pintype "bidirectional"))
      (node (ref "JP1") (pin "1") (pinfunction "1_1") (pintype "passive"))
      (node (ref "OK1") (pin "11") (pinfunction "E_11") (pintype "passive"))
      (node (ref "OK1") (pin "13") (pinfunction "E_13") (pintype "passive"))
      (node (ref "OK1") (pin "15") (pinfunction "E_15") (pintype "passive"))
      (node (ref "OK1") (pin "9") (pinfunction "E_9") (pintype "passive"))
      (node (ref "OK2") (pin "11") (pinfunction "E_11") (pintype "passive"))
      (node (ref "OK2") (pin "13") (pinfunction "E_13") (pintype "passive"))
      (node (ref "OK2") (pin "15") (pinfunction "E_15") (pintype "passive"))
      (node (ref "OK2") (pin "9") (pinfunction "E_9") (pintype "passive"))
      (node (ref "U$1") (pin "1") (pinfunction "GND_1") (pintype "power_in"))
      (node (ref "U$1") (pin "2") (pinfunction "GND_2") (pintype "power_in"))
      (node (ref "U$1") (pin "47") (pinfunction "GND_47") (pintype "power_in"))
      (node (ref "U$1") (pin "48") (pinfunction "GND_48") (pintype "power_in"))
      (node (ref "U$1") (pin "89") (pinfunction "GND_89") (pintype "power_in"))
      (node (ref "U$1") (pin "90") (pinfunction "GND_90") (pintype "power_in"))
      (node (ref "U$1") (pin "91") (pinfunction "GND_91") (pintype "power_in"))
      (node (ref "U$1") (pin "92") (pinfunction "GND_92") (pintype "power_in"))
    )
    (net (code "48") (name "Net-(IC4-C1+)") (class "Default")
      (node (ref "C8") (pin "1") (pinfunction "1_1") (pintype "passive"))
      (node (ref "IC4") (pin "1") (pinfunction "C1+_1") (pintype "passive"))
    )
    (net (code "49") (name "Net-(IC4-C1-)") (class "Default")
      (node (ref "C8") (pin "2") (pinfunction "2_2") (pintype "passive"))
      (node (ref "IC4") (pin "3") (pinfunction "C1-_3") (pintype "passive"))
    )
    (net (code "50") (name "Net-(IC4-C2+)") (class "Default")
      (node (ref "C9") (pin "1") (pinfunction "1_1") (pintype "passive"))
      (node (ref "IC4") (pin "4") (pinfunction "C2+_4") (pintype "passive"))
    )
    (net (code "51") (name "Net-(IC4-C2-)") (class "Default")
      (node (ref "C9") (pin "2") (pinfunction "2_2") (pintype "passive"))
      (node (ref "IC4") (pin "5") (pinfunction "C2-_5") (pintype "passive"))
    )
    (net (code "52") (name "Net-(IC4-V+)") (class "Default")
      (node (ref "C11") (pin "2") (pinfunction "2_2") (pintype "passive"))
      (node (ref "IC4") (pin "2") (pinfunction "V+_2") (pintype "power_in"))
    )
    (net (code "53") (name "Net-(IC4-V-)") (class "Default")
      (node (ref "C10") (pin "1") (pinfunction "1_1") (pintype "passive"))
      (node (ref "IC4") (pin "6") (pinfunction "V-_6") (pintype "power_in"))
    )
    (net (code "54") (name "Net-(IN1A-KL)") (class "Default")
      (node (ref "IN1") (pin "1") (pinfunction "KL_1") (pintype "passive"))
      (node (ref "R1") (pin "1") (pinfunction "1_1") (pintype "passive"))
    )
    (net (code "55") (name "Net-(IN1B-KL)") (class "Default")
      (node (ref "IN1") (pin "2") (pinfunction "KL_2") (pintype "passive"))
      (node (ref "OK1") (pin "2") (pinfunction "AC2_2") (pintype "passive"))
    )
    (net (code "56") (name "Net-(IN2A-KL)") (class "Default")
      (node (ref "IN2") (pin "1") (pinfunction "KL_1") (pintype "passive"))
      (node (ref "R2") (pin "1") (pinfunction "1_1") (pintype "passive"))
    )
    (net (code "57") (name "Net-(IN2B-KL)") (class "Default")
      (node (ref "IN2") (pin "2") (pinfunction "KL_2") (pintype "passive"))
      (node (ref "OK1") (pin "4") (pinfunction "AC2_4") (pintype "passive"))
    )
    (net (code "58") (name "Net-(IN3A-KL)") (class "Default")
      (node (ref "IN3") (pin "1") (pinfunction "KL_1") (pintype "passive"))
      (node (ref "R3") (pin "1") (pinfunction "1_1") (pintype "passive"))
    )
    (net (code "59") (name "Net-(IN3B-KL)") (class "Default")
      (node (ref "IN3") (pin "2") (pinfunction "KL_2") (pintype "passive"))
      (node (ref "OK1") (pin "6") (pinfunction "AC2_6") (pintype "passive"))
    )
    (net (code "60") (name "Net-(IN4A-KL)") (class "Default")
      (node (ref "IN4") (pin "1") (pinfunction "KL_1") (pintype "passive"))
      (node (ref "R4") (pin "1") (pinfunction "1_1") (pintype "passive"))
    )
    (net (code "61") (name "Net-(IN4B-KL)") (class "Default")
      (node (ref "IN4") (pin "2") (pinfunction "KL_2") (pintype "passive"))
      (node (ref "OK1") (pin "8") (pinfunction "AC2_8") (pintype "passive"))
    )
    (net (code "62") (name "Net-(IN5A-KL)") (class "Default")
      (node (ref "IN5") (pin "1") (pinfunction "KL_1") (pintype "passive"))
      (node (ref "R5") (pin "1") (pinfunction "1_1") (pintype "passive"))
    )
    (net (code "63") (name "Net-(IN5B-KL)") (class "Default")
      (node (ref "IN5") (pin "2") (pinfunction "KL_2") (pintype "passive"))
      (node (ref "OK2") (pin "2") (pinfunction "AC2_2") (pintype "passive"))
    )
    (net (code "64") (name "Net-(IN6A-KL)") (class "Default")
      (node (ref "IN6") (pin "1") (pinfunction "KL_1") (pintype "passive"))
      (node (ref "R6") (pin "1") (pinfunction "1_1") (pintype "passive"))
    )
    (net (code "65") (name "Net-(IN6B-KL)") (class "Default")
      (node (ref "IN6") (pin "2") (pinfunction "KL_2") (pintype "passive"))
      (node (ref "OK2") (pin "4") (pinfunction "AC2_4") (pintype "passive"))
    )
    (net (code "66") (name "Net-(IN7A-KL)") (class "Default")
      (node (ref "IN7") (pin "1") (pinfunction "KL_1") (pintype "passive"))
      (node (ref "R7") (pin "1") (pinfunction "1_1") (pintype "passive"))
    )
    (net (code "67") (name "Net-(IN7B-KL)") (class "Default")
      (node (ref "IN7") (pin "2") (pinfunction "KL_2") (pintype "passive"))
      (node (ref "OK2") (pin "6") (pinfunction "AC2_6") (pintype "passive"))
    )
    (net (code "68") (name "Net-(IN8A-KL)") (class "Default")
      (node (ref "IN8") (pin "1") (pinfunction "KL_1") (pintype "passive"))
      (node (ref "R8") (pin "1") (pinfunction "1_1") (pintype "passive"))
    )
    (net (code "69") (name "Net-(IN8B-KL)") (class "Default")
      (node (ref "IN8") (pin "2") (pinfunction "KL_2") (pintype "passive"))
      (node (ref "OK2") (pin "8") (pinfunction "AC2_8") (pintype "passive"))
    )
    (net (code "70") (name "Net-(TP23-PadTP)") (class "Default")
      (node (ref "TP23") (pin "TP") (pinfunction "TP_TP") (pintype "input"))
      (node (ref "U$1") (pin "53") (pinfunction "SYS_5V_53") (pintype "power_in"))
    )
    (net (code "71") (name "Net-(TP34-PadTP)") (class "Default")
      (node (ref "TP34") (pin "TP") (pinfunction "TP_TP") (pintype "input"))
      (node (ref "U$1") (pin "54") (pinfunction "SYS_5V_54") (pintype "passive"))
    )
    (net (code "72") (name "Net-(U$1-AIN0)") (class "Default")
      (node (ref "TP33") (pin "TP") (pinfunction "TP_TP") (pintype "input"))
      (node (ref "U$1") (pin "85") (pinfunction "AIN0_85") (pintype "power_in"))
    )
    (net (code "73") (name "Net-(U$1-AIN1)") (class "Default")
      (node (ref "TP45") (pin "TP") (pinfunction "TP_TP") (pintype "input"))
      (node (ref "U$1") (pin "86") (pinfunction "AIN1_86") (pintype "passive"))
    )
    (net (code "74") (name "Net-(U$1-AIN2)") (class "Default")
      (node (ref "TP32") (pin "TP") (pinfunction "TP_TP") (pintype "input"))
      (node (ref "U$1") (pin "83") (pinfunction "AIN2_83") (pintype "passive"))
    )
    (net (code "75") (name "Net-(U$1-AIN3)") (class "Default")
      (node (ref "TP44") (pin "TP") (pinfunction "TP_TP") (pintype "input"))
      (node (ref "U$1") (pin "84") (pinfunction "AIN3_84") (pintype "passive"))
    )
    (net (code "76") (name "Net-(U$1-AIN4)") (class "Default")
      (node (ref "TP30") (pin "TP") (pinfunction "TP_TP") (pintype "input"))
      (node (ref "U$1") (pin "79") (pinfunction "AIN4_79") (pintype "passive"))
    )
    (net (code "77") (name "Net-(U$1-AIN5)") (class "Default")
      (node (ref "TP43") (pin "TP") (pinfunction "TP_TP") (pintype "input"))
      (node (ref "U$1") (pin "82") (pinfunction "AIN5_82") (pintype "passive"))
    )
    (net (code "78") (name "Net-(U$1-AIN6)") (class "Default")
      (node (ref "TP31") (pin "TP") (pinfunction "TP_TP") (pintype "input"))
      (node (ref "U$1") (pin "81") (pinfunction "AIN6_81") (pintype "passive"))
    )
    (net (code "79") (name "Net-(U$1-EHRPWM1A)") (class "Default")
      (node (ref "TP36") (pin "TP") (pinfunction "TP_TP") (pintype "input"))
      (node (ref "U$1") (pin "60") (pinfunction "EHRPWM1A_60") (pintype "passive"))
    )
    (net (code "80") (name "Net-(U$1-EHRPWM1B)") (class "Default")
      (node (ref "TP37") (pin "TP") (pinfunction "TP_TP") (pintype "input"))
      (node (ref "U$1") (pin "62") (pinfunction "EHRPWM1B_62") (pintype "passive"))
    )
    (net (code "81") (name "Net-(U$1-EHRPWM2A)") (class "Default")
      (node (ref "TP21") (pin "TP") (pinfunction "TP_TP") (pintype "input"))
      (node (ref "U$1") (pin "19") (pinfunction "EHRPWM2A_19") (pintype "passive"))
    )
    (net (code "82") (name "Net-(U$1-EHRPWM2B)") (class "Default")
      (node (ref "TP8") (pin "TP") (pinfunction "TP_TP") (pintype "input"))
      (node (ref "U$1") (pin "13") (pinfunction "EHRPWM2B_13") (pintype "passive"))
    )
    (net (code "83") (name "Net-(U$1-GNDA_ADC)") (class "Default")
      (node (ref "TP42") (pin "TP") (pinfunction "TP_TP") (pintype "input"))
      (node (ref "U$1") (pin "80") (pinfunction "GNDA_ADC_80") (pintype "passive"))
    )
    (net (code "84") (name "Net-(U$1-GPIO1_0)") (class "Default")
      (node (ref "TP11") (pin "TP") (pinfunction "TP_TP") (pintype "input"))
      (node (ref "U$1") (pin "25") (pinfunction "GPIO1_0_25") (pintype "passive"))
    )
    (net (code "85") (name "Net-(U$1-GPIO1_1)") (class "Default")
      (node (ref "TP51") (pin "TP") (pinfunction "TP_TP") (pintype "input"))
      (node (ref "U$1") (pin "24") (pinfunction "GPIO1_1_24") (pintype "passive"))
    )
    (net (code "86") (name "Net-(U$1-GPIO1_2)") (class "Default")
      (node (ref "TP6") (pin "TP") (pinfunction "TP_TP") (pintype "input"))
      (node (ref "U$1") (pin "5") (pinfunction "GPIO1_2_5") (pintype "passive"))
    )
    (net (code "87") (name "Net-(U$1-GPIO1_3)") (class "Default")
      (node (ref "TP47") (pin "TP") (pinfunction "TP_TP") (pintype "input"))
      (node (ref "U$1") (pin "6") (pinfunction "GPIO1_3_6") (pintype "passive"))
    )
    (net (code "88") (name "Net-(U$1-GPIO1_4)") (class "Default")
      (node (ref "TP10") (pin "TP") (pinfunction "TP_TP") (pintype "input"))
      (node (ref "U$1") (pin "23") (pinfunction "GPIO1_4_23") (pintype "passive"))
    )
    (net (code "89") (name "Net-(U$1-GPIO1_5)") (class "Default")
      (node (ref "TP50") (pin "TP") (pinfunction "TP_TP") (pintype "input"))
      (node (ref "U$1") (pin "22") (pinfunction "GPIO1_5_22") (pintype "passive"))
    )
    (net (code "90") (name "Net-(U$1-GPIO1_6)") (class "Default")
      (node (ref "TP5") (pin "TP") (pinfunction "TP_TP") (pintype "input"))
      (node (ref "U$1") (pin "3") (pinfunction "GPIO1_6_3") (pintype "passive"))
    )
    (net (code "91") (name "Net-(U$1-GPIO1_7)") (class "Default")
      (node (ref "TP46") (pin "TP") (pinfunction "TP_TP") (pintype "input"))
      (node (ref "U$1") (pin "4") (pinfunction "GPIO1_7_4") (pintype "passive"))
    )
    (net (code "92") (name "Net-(U$1-GPIO1_30)") (class "Default")
      (node (ref "TP9") (pin "TP") (pinfunction "TP_TP") (pintype "input"))
      (node (ref "U$1") (pin "21") (pinfunction "GPIO1_30_21") (pintype "passive"))
    )
    (net (code "93") (name "Net-(U$1-GPIO1_31)") (class "Default")
      (node (ref "TP49") (pin "TP") (pinfunction "TP_TP") (pintype "input"))
      (node (ref "U$1") (pin "20") (pinfunction "GPIO1_31_20") (pintype "passive"))
    )
    (net (code "94") (name "Net-(U$1-GPIO2_6)") (class "Default")
      (node (ref "TP22") (pin "TP") (pinfunction "TP_TP") (pintype "input"))
      (node (ref "U$1") (pin "45") (pinfunction "GPIO2_6_45") (pintype "passive"))
    )
    (net (code "95") (name "Net-(U$1-GPIO2_7)") (class "Default")
      (node (ref "TP61") (pin "TP") (pinfunction "TP_TP") (pintype "input"))
      (node (ref "U$1") (pin "46") (pinfunction "GPIO2_7_46") (pintype "passive"))
    )
    (net (code "96") (name "Net-(U$1-GPIO2_8)") (class "Default")
      (node (ref "TP20") (pin "TP") (pinfunction "TP_TP") (pintype "input"))
      (node (ref "U$1") (pin "43") (pinfunction "GPIO2_8_43") (pintype "passive"))
    )
    (net (code "97") (name "Net-(U$1-GPIO2_9)") (class "Default")
      (node (ref "TP60") (pin "TP") (pinfunction "TP_TP") (pintype "input"))
      (node (ref "U$1") (pin "44") (pinfunction "GPIO2_9_44") (pintype "passive"))
    )
    (net (code "98") (name "Net-(U$1-GPIO2_10)") (class "Default")
      (node (ref "TP19") (pin "TP") (pinfunction "TP_TP") (pintype "input"))
      (node (ref "U$1") (pin "41") (pinfunction "GPIO2_10_41") (pintype "passive"))
    )
    (net (code "99") (name "Net-(U$1-GPIO2_11)") (class "Default")
      (node (ref "TP59") (pin "TP") (pinfunction "TP_TP") (pintype "input"))
      (node (ref "U$1") (pin "42") (pinfunction "GPIO2_11_42") (pintype "passive"))
    )
    (net (code "100") (name "Net-(U$1-GPIO2_12)") (class "Default")
      (node (ref "TP18") (pin "TP") (pinfunction "TP_TP") (pintype "input"))
      (node (ref "U$1") (pin "39") (pinfunction "GPIO2_12_39") (pintype "passive"))
    )
    (net (code "101") (name "Net-(U$1-GPIO2_13)") (class "Default")
      (node (ref "TP58") (pin "TP") (pinfunction "TP_TP") (pintype "input"))
      (node (ref "U$1") (pin "40") (pinfunction "GPIO2_13_40") (pintype "passive"))
    )
    (net (code "102") (name "Net-(U$1-GPIO2_22)") (class "Default")
      (node (ref "TP12") (pin "TP") (pinfunction "TP_TP") (pintype "input"))
      (node (ref "U$1") (pin "27") (pinfunction "GPIO2_22_27") (pintype "passive"))
    )
    (net (code "103") (name "Net-(U$1-GPIO2_23)") (class "Default")
      (node (ref "TP13") (pin "TP") (pinfunction "TP_TP") (pintype "input"))
      (node (ref "U$1") (pin "29") (pinfunction "GPIO2_23_29") (pintype "passive"))
    )
    (net (code "104") (name "Net-(U$1-GPIO2_25)") (class "Default")
      (node (ref "TP53") (pin "TP") (pinfunction "TP_TP") (pintype "input"))
      (node (ref "U$1") (pin "30") (pinfunction "GPIO2_25_30") (pintype "passive"))
    )
    (net (code "105") (name "Net-(U$1-GPIO3_21)") (class "Default")
      (node (ref "TP27") (pin "TP") (pinfunction "TP_TP") (pintype "input"))
      (node (ref "U$1") (pin "71") (pinfunction "GPIO3_21_71") (pintype "passive"))
    )
    (net (code "106") (name "Net-(U$1-PWR_BUT)") (class "Default")
      (node (ref "JP1") (pin "2") (pinfunction "2_2") (pintype "passive"))
      (node (ref "U$1") (pin "55") (pinfunction "PWR_BUT_55") (pintype "passive"))
    )
    (net (code "107") (name "Net-(U$1-SPI1_CS0)") (class "Default")
      (node (ref "TP39") (pin "TP") (pinfunction "TP_TP") (pintype "input"))
      (node (ref "U$1") (pin "74") (pinfunction "SPI1_CS0_74") (pintype "passive"))
    )
    (net (code "108") (name "Net-(U$1-SPI1_DI)") (class "Default")
      (node (ref "TP40") (pin "TP") (pinfunction "TP_TP") (pintype "input"))
      (node (ref "U$1") (pin "76") (pinfunction "SPI1_DI_76") (pintype "passive"))
    )
    (net (code "109") (name "Net-(U$1-SPI1_DO)") (class "Default")
      (node (ref "TP28") (pin "TP") (pinfunction "TP_TP") (pintype "input"))
      (node (ref "U$1") (pin "75") (pinfunction "SPI1_DO_75") (pintype "passive"))
    )
    (net (code "110") (name "Net-(U$1-SPI1_SCLK)") (class "Default")
      (node (ref "TP29") (pin "TP") (pinfunction "TP_TP") (pintype "input"))
      (node (ref "U$1") (pin "77") (pinfunction "SPI1_SCLK_77") (pintype "passive"))
    )
    (net (code "111") (name "Net-(U$1-SYS_RESETN)") (class "Default")
      (node (ref "TP35") (pin "TP") (pinfunction "TP_TP") (pintype "input"))
      (node (ref "U$1") (pin "56") (pinfunction "SYS_RESETN_56") (pintype "passive"))
    )
    (net (code "112") (name "Net-(U$1-TIMER6)") (class "Default")
      (node (ref "TP48") (pin "TP") (pinfunction "TP_TP") (pintype "input"))
      (node (ref "U$1") (pin "10") (pinfunction "TIMER6_10") (pintype "passive"))
    )
    (net (code "113") (name "Net-(U$1-TIMER7)") (class "Default")
      (node (ref "TP7") (pin "TP") (pinfunction "TP_TP") (pintype "input"))
      (node (ref "U$1") (pin "8") (pinfunction "TIMER7_8") (pintype "passive"))
    )
    (net (code "114") (name "Net-(U$1-UART2_RXD)") (class "Default")
      (node (ref "TP38") (pin "TP") (pinfunction "TP_TP") (pintype "input"))
      (node (ref "U$1") (pin "68") (pinfunction "UART2_RXD_68") (pintype "passive"))
    )
    (net (code "115") (name "Net-(U$1-UART2_TXD)") (class "Default")
      (node (ref "TP26") (pin "TP") (pinfunction "TP_TP") (pintype "input"))
      (node (ref "U$1") (pin "67") (pinfunction "UART2_TXD_67") (pintype "passive"))
    )
    (net (code "116") (name "Net-(U$1-UART3_CTSN)") (class "Default")
      (node (ref "TP56") (pin "TP") (pinfunction "TP_TP") (pintype "input"))
      (node (ref "U$1") (pin "36") (pinfunction "UART3_CTSN_36") (pintype "passive"))
    )
    (net (code "117") (name "Net-(U$1-UART3_RTSN)") (class "Default")
      (node (ref "TP55") (pin "TP") (pinfunction "TP_TP") (pintype "input"))
      (node (ref "U$1") (pin "34") (pinfunction "UART3_RTSN_34") (pintype "passive"))
    )
    (net (code "118") (name "Net-(U$1-UART4_CTSN)") (class "Default")
      (node (ref "TP16") (pin "TP") (pinfunction "TP_TP") (pintype "input"))
      (node (ref "U$1") (pin "35") (pinfunction "UART4_CTSN_35") (pintype "passive"))
    )
    (net (code "119") (name "Net-(U$1-UART4_RTSN)") (class "Default")
      (node (ref "TP15") (pin "TP") (pinfunction "TP_TP") (pintype "input"))
      (node (ref "U$1") (pin "33") (pinfunction "UART4_RTSN_33") (pintype "passive"))
    )
    (net (code "120") (name "Net-(U$1-UART4_RXD)") (class "Default")
      (node (ref "TP24") (pin "TP") (pinfunction "TP_TP") (pintype "input"))
      (node (ref "U$1") (pin "57") (pinfunction "UART4_RXD_57") (pintype "passive"))
    )
    (net (code "121") (name "Net-(U$1-UART4_TXD)") (class "Default")
      (node (ref "TP25") (pin "TP") (pinfunction "TP_TP") (pintype "input"))
      (node (ref "U$1") (pin "59") (pinfunction "UART4_TXD_59") (pintype "passive"))
    )
    (net (code "122") (name "Net-(U$1-UART5_CTSN)") (class "Default")
      (node (ref "TP14") (pin "TP") (pinfunction "TP_TP") (pintype "input"))
      (node (ref "U$1") (pin "31") (pinfunction "UART5_CTSN_31") (pintype "passive"))
    )
    (net (code "123") (name "Net-(U$1-UART5_RTSN)") (class "Default")
      (node (ref "TP54") (pin "TP") (pinfunction "TP_TP") (pintype "input"))
      (node (ref "U$1") (pin "32") (pinfunction "UART5_RTSN_32") (pintype "passive"))
    )
    (net (code "124") (name "Net-(U$1-UART5_RXD)") (class "Default")
      (node (ref "TP57") (pin "TP") (pinfunction "TP_TP") (pintype "input"))
      (node (ref "U$1") (pin "38") (pinfunction "UART5_RXD_38") (pintype "passive"))
    )
    (net (code "125") (name "Net-(U$1-UART5_TXD)") (class "Default")
      (node (ref "TP17") (pin "TP") (pinfunction "TP_TP") (pintype "input"))
      (node (ref "U$1") (pin "37") (pinfunction "UART5_TXD_37") (pintype "passive"))
    )
    (net (code "126") (name "Net-(U$1-VDD_ADC)") (class "Default")
      (node (ref "TP41") (pin "TP") (pinfunction "TP_TP") (pintype "input"))
      (node (ref "U$1") (pin "78") (pinfunction "VDD_ADC_78") (pintype "passive"))
    )
    (net (code "127") (name "Net-(X1A-KL)") (class "Default")
      (node (ref "K1") (pin "S") (pinfunction "S_S") (pintype "passive"))
      (node (ref "X1") (pin "1") (pinfunction "KL_1") (pintype "passive"))
    )
    (net (code "128") (name "Net-(X1B-KL)") (class "Default")
      (node (ref "K1") (pin "P") (pinfunction "P_P") (pintype "passive"))
      (node (ref "X1") (pin "2") (pinfunction "KL_2") (pintype "passive"))
    )
    (net (code "129") (name "Net-(X1C-KL)") (class "Default")
      (node (ref "K1") (pin "O") (pinfunction "O_O") (pintype "passive"))
      (node (ref "X1") (pin "3") (pinfunction "KL_3") (pintype "passive"))
    )
    (net (code "130") (name "Net-(X2A-KL)") (class "Default")
      (node (ref "K2") (pin "S") (pinfunction "S_S") (pintype "passive"))
      (node (ref "X2") (pin "1") (pinfunction "KL_1") (pintype "passive"))
    )
    (net (code "131") (name "Net-(X2B-KL)") (class "Default")
      (node (ref "K2") (pin "P") (pinfunction "P_P") (pintype "passive"))
      (node (ref "X2") (pin "2") (pinfunction "KL_2") (pintype "passive"))
    )
    (net (code "132") (name "Net-(X2C-KL)") (class "Default")
      (node (ref "K2") (pin "O") (pinfunction "O_O") (pintype "passive"))
      (node (ref "X2") (pin "3") (pinfunction "KL_3") (pintype "passive"))
    )
    (net (code "133") (name "Net-(X3A-KL)") (class "Default")
      (node (ref "K3") (pin "S") (pinfunction "S_S") (pintype "passive"))
      (node (ref "X3") (pin "1") (pinfunction "KL_1") (pintype "passive"))
    )
    (net (code "134") (name "Net-(X3B-KL)") (class "Default")
      (node (ref "K3") (pin "P") (pinfunction "P_P") (pintype "passive"))
      (node (ref "X3") (pin "2") (pinfunction "KL_2") (pintype "passive"))
    )
    (net (code "135") (name "Net-(X3C-KL)") (class "Default")
      (node (ref "K3") (pin "O") (pinfunction "O_O") (pintype "passive"))
      (node (ref "X3") (pin "3") (pinfunction "KL_3") (pintype "passive"))
    )
    (net (code "136") (name "Net-(X4A-KL)") (class "Default")
      (node (ref "K4") (pin "S") (pinfunction "S_S") (pintype "passive"))
      (node (ref "X4") (pin "1") (pinfunction "KL_1") (pintype "passive"))
    )
    (net (code "137") (name "Net-(X4B-KL)") (class "Default")
      (node (ref "K4") (pin "P") (pinfunction "P_P") (pintype "passive"))
      (node (ref "X4") (pin "2") (pinfunction "KL_2") (pintype "passive"))
    )
    (net (code "138") (name "Net-(X4C-KL)") (class "Default")
      (node (ref "K4") (pin "O") (pinfunction "O_O") (pintype "passive"))
      (node (ref "X4") (pin "3") (pinfunction "KL_3") (pintype "passive"))
    )
    (net (code "139") (name "Net-(X5A-KL)") (class "Default")
      (node (ref "K5") (pin "S") (pinfunction "S_S") (pintype "passive"))
      (node (ref "X5") (pin "1") (pinfunction "KL_1") (pintype "passive"))
    )
    (net (code "140") (name "Net-(X5B-KL)") (class "Default")
      (node (ref "K5") (pin "P") (pinfunction "P_P") (pintype "passive"))
      (node (ref "X5") (pin "2") (pinfunction "KL_2") (pintype "passive"))
    )
    (net (code "141") (name "Net-(X5C-KL)") (class "Default")
      (node (ref "K5") (pin "O") (pinfunction "O_O") (pintype "passive"))
      (node (ref "X5") (pin "3") (pinfunction "KL_3") (pintype "passive"))
    )
    (net (code "142") (name "Net-(X6A-KL)") (class "Default")
      (node (ref "K6") (pin "S") (pinfunction "S_S") (pintype "passive"))
      (node (ref "X6") (pin "1") (pinfunction "KL_1") (pintype "passive"))
    )
    (net (code "143") (name "Net-(X6B-KL)") (class "Default")
      (node (ref "K6") (pin "P") (pinfunction "P_P") (pintype "passive"))
      (node (ref "X6") (pin "2") (pinfunction "KL_2") (pintype "passive"))
    )
    (net (code "144") (name "Net-(X6C-KL)") (class "Default")
      (node (ref "K6") (pin "O") (pinfunction "O_O") (pintype "passive"))
      (node (ref "X6") (pin "3") (pinfunction "KL_3") (pintype "passive"))
    )
    (net (code "145") (name "Net-(X7A-KL)") (class "Default")
      (node (ref "K7") (pin "S") (pinfunction "S_S") (pintype "passive"))
      (node (ref "X7") (pin "1") (pinfunction "KL_1") (pintype "passive"))
    )
    (net (code "146") (name "Net-(X7B-KL)") (class "Default")
      (node (ref "K7") (pin "P") (pinfunction "P_P") (pintype "passive"))
      (node (ref "X7") (pin "2") (pinfunction "KL_2") (pintype "passive"))
    )
    (net (code "147") (name "Net-(X7C-KL)") (class "Default")
      (node (ref "K7") (pin "O") (pinfunction "O_O") (pintype "passive"))
      (node (ref "X7") (pin "3") (pinfunction "KL_3") (pintype "passive"))
    )
    (net (code "148") (name "Net-(X8A-KL)") (class "Default")
      (node (ref "K8") (pin "S") (pinfunction "S_S") (pintype "passive"))
      (node (ref "X8") (pin "1") (pinfunction "KL_1") (pintype "passive"))
    )
    (net (code "149") (name "Net-(X8B-KL)") (class "Default")
      (node (ref "K8") (pin "P") (pinfunction "P_P") (pintype "passive"))
      (node (ref "X8") (pin "2") (pinfunction "KL_2") (pintype "passive"))
    )
    (net (code "150") (name "Net-(X8C-KL)") (class "Default")
      (node (ref "K8") (pin "O") (pinfunction "O_O") (pintype "passive"))
      (node (ref "X8") (pin "3") (pinfunction "KL_3") (pintype "passive"))
    )
    (net (code "151") (name "Net-(X10A-KL)") (class "Default")
      (node (ref "TP1") (pin "TP") (pinfunction "TP_TP") (pintype "input"))
      (node (ref "X10") (pin "1") (pinfunction "KL_1") (pintype "passive"))
    )
    (net (code "152") (name "Net-(X10B-KL)") (class "Default")
      (node (ref "TP2") (pin "TP") (pinfunction "TP_TP") (pintype "input"))
      (node (ref "X10") (pin "2") (pinfunction "KL_2") (pintype "passive"))
    )
    (net (code "153") (name "Net-(X11A-KL)") (class "Default")
      (node (ref "TP3") (pin "TP") (pinfunction "TP_TP") (pintype "input"))
      (node (ref "X11") (pin "1") (pinfunction "KL_1") (pintype "passive"))
    )
    (net (code "154") (name "Net-(X11B-KL)") (class "Default")
      (node (ref "TP4") (pin "TP") (pinfunction "TP_TP") (pintype "input"))
      (node (ref "X11") (pin "2") (pinfunction "KL_2") (pintype "passive"))
    )
    (net (code "155") (name "unconnected-(IC4-R2IN-Pad8)") (class "Default")
      (node (ref "IC4") (pin "8") (pinfunction "R2IN_8") (pintype "input"))
    )
    (net (code "156") (name "unconnected-(IC4-R2OUT-Pad9)") (class "Default")
      (node (ref "IC4") (pin "9") (pinfunction "R2OUT_9") (pintype "output"))
    )
    (net (code "157") (name "unconnected-(IC4-T2IN-Pad10)") (class "Default")
      (node (ref "IC4") (pin "10") (pinfunction "T2IN_10") (pintype "input"))
    )
    (net (code "158") (name "unconnected-(IC4-T2OUT-Pad7)") (class "Default")
      (node (ref "IC4") (pin "7") (pinfunction "T2OUT_7") (pintype "output"))
    )
    (net (code "159") (name "unconnected-(J1-Pad4)") (class "Default")
      (node (ref "J1") (pin "4") (pinfunction "4_4") (pintype "bidirectional"))
    )
  )
)
